# DI_ch.net
KiCad netlist of a schematic drawn in Altium Designer
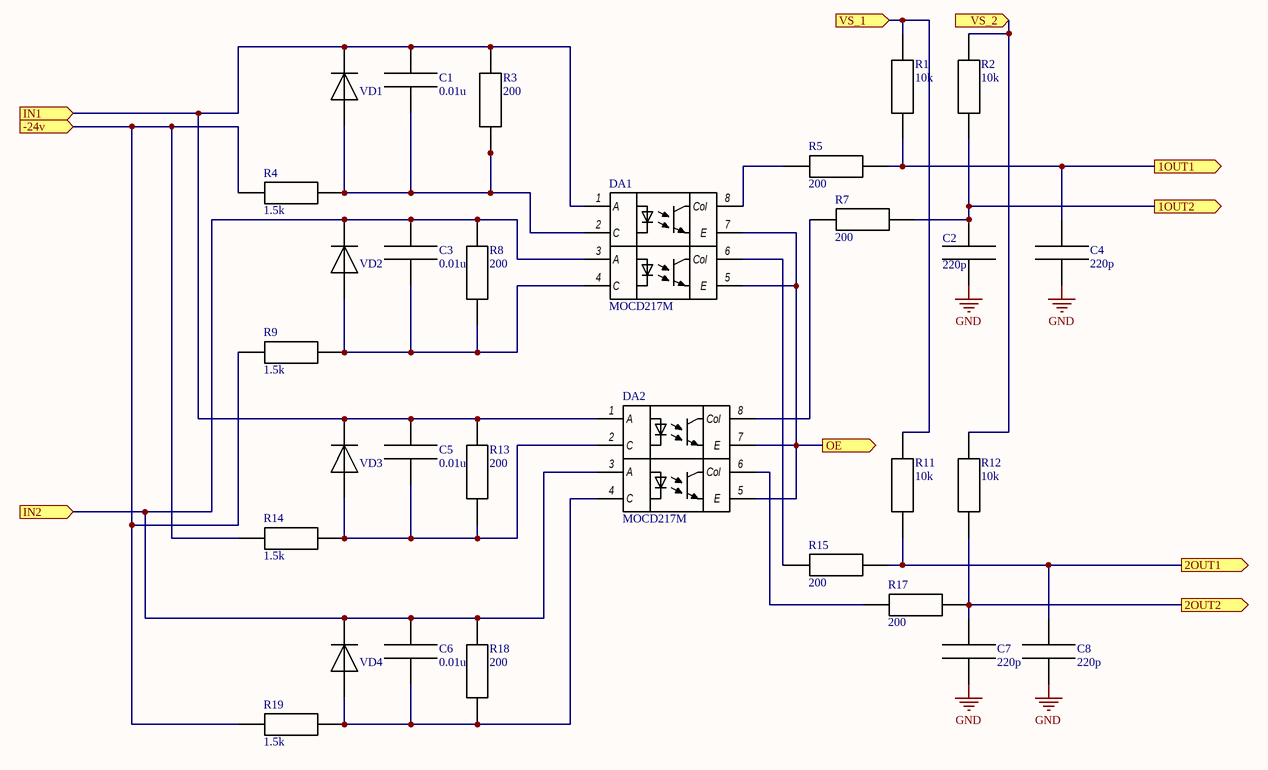
[diagram p0: DI_ch.SchDoc]

(export (version "E")
  (design (tool "Eeschema 10.0.6"))
  (components
    (comp (ref "C1") (value "0.01u") (footprint "0603_cap") (libsource (lib "lib") (part "cap")))
    (comp (ref "C2") (value "220p") (footprint "cap_0402") (libsource (lib "lib") (part "cap")))
    (comp (ref "C3") (value "0.01u") (footprint "0603_cap") (libsource (lib "lib") (part "cap")))
    (comp (ref "C4") (value "220p") (footprint "cap_0402") (libsource (lib "lib") (part "cap")))
    (comp (ref "C5") (value "0.01u") (footprint "0603_cap") (libsource (lib "lib") (part "cap")))
    (comp (ref "C6") (value "0.01u") (footprint "0603_cap") (libsource (lib "lib") (part "cap")))
    (comp (ref "C7") (value "220p") (footprint "cap_0402") (libsource (lib "lib") (part "cap")))
    (comp (ref "C8") (value "220p") (footprint "cap_0402") (libsource (lib "lib") (part "cap")))
    (comp (ref "DA1")
      (value "MOCD217M")
      (footprint "SO-8_optocup")
      (description "dual optopair")
      (libsource (lib "lib") (part "MOCD217M"))
    )
    (comp (ref "DA2")
      (value "MOCD217M")
      (footprint "SO-8_optocup")
      (description "dual optopair")
      (libsource (lib "lib") (part "MOCD217M"))
    )
    (comp (ref "R1") (value "10k") (footprint "res_0402") (libsource (lib "lib") (part "res")))
    (comp (ref "R2") (value "10k") (footprint "res_0402") (libsource (lib "lib") (part "res")))
    (comp (ref "R3") (value "200") (footprint "0603_res") (libsource (lib "lib") (part "res")))
    (comp (ref "R4") (value "1.5k") (footprint "2512_res") (libsource (lib "lib") (part "res")))
    (comp (ref "R5") (value "200") (footprint "res_0402") (libsource (lib "lib") (part "res")))
    (comp (ref "R7") (value "200") (footprint "res_0402") (libsource (lib "lib") (part "res")))
    (comp (ref "R8") (value "200") (footprint "0603_res") (libsource (lib "lib") (part "res")))
    (comp (ref "R9") (value "1.5k") (footprint "2512_res") (libsource (lib "lib") (part "res")))
    (comp (ref "R11") (value "10k") (footprint "res_0402") (libsource (lib "lib") (part "res")))
    (comp (ref "R12") (value "10k") (footprint "res_0402") (libsource (lib "lib") (part "res")))
    (comp (ref "R13") (value "200") (footprint "0603_res") (libsource (lib "lib") (part "res")))
    (comp (ref "R14") (value "1.5k") (footprint "2512_res") (libsource (lib "lib") (part "res")))
    (comp (ref "R15") (value "200") (footprint "res_0402") (libsource (lib "lib") (part "res")))
    (comp (ref "R17") (value "200") (footprint "res_0402") (libsource (lib "lib") (part "res")))
    (comp (ref "R18") (value "200") (footprint "0603_res") (libsource (lib "lib") (part "res")))
    (comp (ref "R19") (value "1.5k") (footprint "2512_res") (libsource (lib "lib") (part "res")))
    (comp (ref "VD1") (value "1N4448") (footprint "sod-323") (libsource (lib "lib") (part "1N4448")))
    (comp (ref "VD2") (value "1N4448") (footprint "sod-323") (libsource (lib "lib") (part "1N4448")))
    (comp (ref "VD3") (value "1N4448") (footprint "sod-323") (libsource (lib "lib") (part "1N4448")))
    (comp (ref "VD4") (value "1N4448") (footprint "sod-323") (libsource (lib "lib") (part "1N4448")))
  )
  (nets
    (net (code "1") (name "/-24v") (class "Default")
      (node (ref "R14") (pin "1") (pinfunction "1_1") (pintype "passive"))
      (node (ref "R19") (pin "1") (pinfunction "1_1") (pintype "passive"))
      (node (ref "R4") (pin "1") (pinfunction "1_1") (pintype "passive"))
      (node (ref "R9") (pin "1") (pinfunction "1_1") (pintype "passive"))
    )
    (net (code "2") (name "/1OUT1") (class "Default")
      (node (ref "C4") (pin "2") (pinfunction "2_2") (pintype "passive"))
      (node (ref "R1") (pin "1") (pinfunction "1_1") (pintype "passive"))
      (node (ref "R5") (pin "1") (pinfunction "1_1") (pintype "passive"))
    )
    (net (code "3") (name "/1OUT2") (class "Default")
      (node (ref "C2") (pin "2") (pinfunction "2_2") (pintype "passive"))
      (node (ref "R2") (pin "1") (pinfunction "1_1") (pintype "passive"))
      (node (ref "R7") (pin "1") (pinfunction "1_1") (pintype "passive"))
    )
    (net (code "4") (name "/2OUT1") (class "Default")
      (node (ref "C8") (pin "2") (pinfunction "2_2") (pintype "passive"))
      (node (ref "R11") (pin "1") (pinfunction "1_1") (pintype "passive"))
      (node (ref "R15") (pin "1") (pinfunction "1_1") (pintype "passive"))
    )
    (net (code "5") (name "/2OUT2") (class "Default")
      (node (ref "C7") (pin "2") (pinfunction "2_2") (pintype "passive"))
      (node (ref "R12") (pin "1") (pinfunction "1_1") (pintype "passive"))
      (node (ref "R17") (pin "1") (pinfunction "1_1") (pintype "passive"))
    )
    (net (code "6") (name "/IN1") (class "Default")
      (node (ref "C1") (pin "2") (pinfunction "2_2") (pintype "passive"))
      (node (ref "C5") (pin "2") (pinfunction "2_2") (pintype "passive"))
      (node (ref "DA1") (pin "1") (pinfunction "A_1") (pintype "passive"))
      (node (ref "DA2") (pin "1") (pinfunction "A_1") (pintype "passive"))
      (node (ref "R13") (pin "2") (pinfunction "2_2") (pintype "passive"))
      (node (ref "R3") (pin "2") (pinfunction "2_2") (pintype "passive"))
      (node (ref "VD1") (pin "K") (pinfunction "K_K") (pintype "passive"))
      (node (ref "VD3") (pin "K") (pinfunction "K_K") (pintype "passive"))
    )
    (net (code "7") (name "/IN2") (class "Default")
      (node (ref "C3") (pin "2") (pinfunction "2_2") (pintype "passive"))
      (node (ref "C6") (pin "2") (pinfunction "2_2") (pintype "passive"))
      (node (ref "DA1") (pin "3") (pinfunction "A_3") (pintype "passive"))
      (node (ref "DA2") (pin "3") (pinfunction "A_3") (pintype "passive"))
      (node (ref "R18") (pin "2") (pinfunction "2_2") (pintype "passive"))
      (node (ref "R8") (pin "2") (pinfunction "2_2") (pintype "passive"))
      (node (ref "VD2") (pin "K") (pinfunction "K_K") (pintype "passive"))
      (node (ref "VD4") (pin "K") (pinfunction "K_K") (pintype "passive"))
    )
    (net (code "8") (name "/OE") (class "Default")
      (node (ref "DA1") (pin "5") (pinfunction "E_5") (pintype "passive"))
      (node (ref "DA1") (pin "7") (pinfunction "E_7") (pintype "passive"))
      (node (ref "DA2") (pin "5") (pinfunction "E_5") (pintype "passive"))
      (node (ref "DA2") (pin "7") (pinfunction "E_7") (pintype "passive"))
    )
    (net (code "9") (name "/VS_1") (class "Default")
      (node (ref "R1") (pin "2") (pinfunction "2_2") (pintype "passive"))
      (node (ref "R11") (pin "2") (pinfunction "2_2") (pintype "passive"))
    )
    (net (code "10") (name "/VS_2") (class "Default")
      (node (ref "R12") (pin "2") (pinfunction "2_2") (pintype "passive"))
      (node (ref "R2") (pin "2") (pinfunction "2_2") (pintype "passive"))
    )
    (net (code "11") (name "GND") (class "Default")
      (node (ref "C2") (pin "1") (pinfunction "1_1") (pintype "passive"))
      (node (ref "C4") (pin "1") (pinfunction "1_1") (pintype "passive"))
      (node (ref "C7") (pin "1") (pinfunction "1_1") (pintype "passive"))
      (node (ref "C8") (pin "1") (pinfunction "1_1") (pintype "passive"))
    )
    (net (code "12") (name "Net-(C1-Pad1)") (class "Default")
      (node (ref "C1") (pin "1") (pinfunction "1_1") (pintype "passive"))
      (node (ref "DA1") (pin "2") (pinfunction "C_2") (pintype "passive"))
      (node (ref "R3") (pin "1") (pinfunction "1_1") (pintype "passive"))
      (node (ref "R4") (pin "2") (pinfunction "2_2") (pintype "passive"))
      (node (ref "VD1") (pin "A") (pinfunction "A_A") (pintype "passive"))
    )
    (net (code "13") (name "Net-(C3-Pad1)") (class "Default")
      (node (ref "C3") (pin "1") (pinfunction "1_1") (pintype "passive"))
      (node (ref "DA1") (pin "4") (pinfunction "C_4") (pintype "passive"))
      (node (ref "R8") (pin "1") (pinfunction "1_1") (pintype "passive"))
      (node (ref "R9") (pin "2") (pinfunction "2_2") (pintype "passive"))
      (node (ref "VD2") (pin "A") (pinfunction "A_A") (pintype "passive"))
    )
    (net (code "14") (name "Net-(C5-Pad1)") (class "Default")
      (node (ref "C5") (pin "1") (pinfunction "1_1") (pintype "passive"))
      (node (ref "DA2") (pin "2") (pinfunction "C_2") (pintype "passive"))
      (node (ref "R13") (pin "1") (pinfunction "1_1") (pintype "passive"))
      (node (ref "R14") (pin "2") (pinfunction "2_2") (pintype "passive"))
      (node (ref "VD3") (pin "A") (pinfunction "A_A") (pintype "passive"))
    )
    (net (code "15") (name "Net-(C6-Pad1)") (class "Default")
      (node (ref "C6") (pin "1") (pinfunction "1_1") (pintype "passive"))
      (node (ref "DA2") (pin "4") (pinfunction "C_4") (pintype "passive"))
      (node (ref "R18") (pin "1") (pinfunction "1_1") (pintype "passive"))
      (node (ref "R19") (pin "2") (pinfunction "2_2") (pintype "passive"))
      (node (ref "VD4") (pin "A") (pinfunction "A_A") (pintype "passive"))
    )
    (net (code "16") (name "Net-(DA1-Col-Pad6)") (class "Default")
      (node (ref "DA1") (pin "6") (pinfunction "Col_6") (pintype "passive"))
      (node (ref "R15") (pin "2") (pinfunction "2_2") (pintype "passive"))
    )
    (net (code "17") (name "Net-(DA1-Col-Pad8)") (class "Default")
      (node (ref "DA1") (pin "8") (pinfunction "Col_8") (pintype "passive"))
      (node (ref "R5") (pin "2") (pinfunction "2_2") (pintype "passive"))
    )
    (net (code "18") (name "Net-(DA2-Col-Pad6)") (class "Default")
      (node (ref "DA2") (pin "6") (pinfunction "Col_6") (pintype "passive"))
      (node (ref "R17") (pin "2") (pinfunction "2_2") (pintype "passive"))
    )
    (net (code "19") (name "Net-(DA2-Col-Pad8)") (class "Default")
      (node (ref "DA2") (pin "8") (pinfunction "Col_8") (pintype "passive"))
      (node (ref "R7") (pin "2") (pinfunction "2_2") (pintype "passive"))
    )
  )
)
